# DB10012_IMUTopLevel.net
KiCad netlist of a schematic drawn in Altium Designer
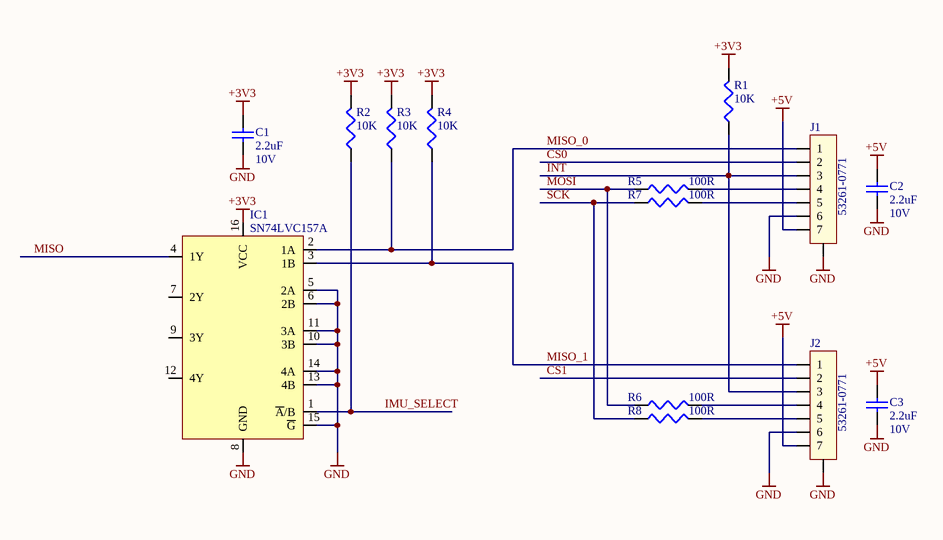
[diagram p0: DB10012_IMUTopLevel.SchDoc]

(export (version "E")
  (design (tool "Eeschema 10.0.6"))
  (components
    (comp (ref "C1")
      (value "2.2uF")
      (footprint "C0603")
      (description "Capacitor, 2.2uF, 10V, X5R")
      (fields (field (name "VOLTAGE RATING") "10V"))
      (libsource (lib "AR_Capacitors_Ceramic") (part "2.2uF/0603/CER/10V/X5R"))
    )
    (comp (ref "C2")
      (value "2.2uF")
      (footprint "C0603")
      (description "Capacitor, 2.2uF, 10V, X5R")
      (fields (field (name "VOLTAGE RATING") "10V"))
      (libsource (lib "AR_Capacitors_Ceramic") (part "2.2uF/0603/CER/10V/X5R"))
    )
    (comp (ref "C3")
      (value "2.2uF")
      (footprint "C0603")
      (description "Capacitor, 2.2uF, 10V, X5R")
      (fields (field (name "VOLTAGE RATING") "10V"))
      (libsource (lib "AR_Capacitors_Ceramic") (part "2.2uF/0603/CER/10V/X5R"))
    )
    (comp (ref "IC1")
      (value "SN74LVC157A")
      (footprint "TSSOP16")
      (description "8:4 DATA SELECTOR/MUX")
      (libsource (lib "AR_ICs") (part "SN74LVC157A"))
    )
    (comp (ref "J1")
      (value "53261-0771")
      (footprint "53261-0771")
      (description "PicoBlade 53261 Series, 7Pin, Right Angle")
      (libsource (lib "AR_Connectors") (part "53261-0771"))
    )
    (comp (ref "J2")
      (value "53261-0771")
      (footprint "53261-0771")
      (description "PicoBlade 53261 Series, 7Pin, Right Angle")
      (libsource (lib "AR_Connectors") (part "53261-0771"))
    )
    (comp (ref "R1")
      (value "10K")
      (footprint "0603")
      (description "Resistor, 10K, 1%, 0.063W, 50V, 100PPM, 0603")
      (libsource (lib "AR_Resistors_SMD") (part "10K/0603/0063W/50V"))
    )
    (comp (ref "R2")
      (value "10K")
      (footprint "0603")
      (description "Resistor, 10K, 1%, 0.063W, 50V, 100PPM, 0603")
      (libsource (lib "AR_Resistors_SMD") (part "10K/0603/0063W/50V"))
    )
    (comp (ref "R3")
      (value "10K")
      (footprint "0603")
      (description "Resistor, 10K, 1%, 0.063W, 50V, 100PPM, 0603")
      (libsource (lib "AR_Resistors_SMD") (part "10K/0603/0063W/50V"))
    )
    (comp (ref "R4")
      (value "10K")
      (footprint "0603")
      (description "Resistor, 10K, 1%, 0.063W, 50V, 100PPM, 0603")
      (libsource (lib "AR_Resistors_SMD") (part "10K/0603/0063W/50V"))
    )
    (comp (ref "R5")
      (value "100R")
      (footprint "0603")
      (description "Resistor, 100R, 1%, 0.063W, 50V, 200PPM, 0603")
      (libsource (lib "AR_Resistors_SMD") (part "100/0603/0063W/50V"))
    )
    (comp (ref "R6")
      (value "100R")
      (footprint "0603")
      (description "Resistor, 100R, 1%, 0.063W, 50V, 200PPM, 0603")
      (libsource (lib "AR_Resistors_SMD") (part "100/0603/0063W/50V"))
    )
    (comp (ref "R7")
      (value "100R")
      (footprint "0603")
      (description "Resistor, 100R, 1%, 0.063W, 50V, 200PPM, 0603")
      (libsource (lib "AR_Resistors_SMD") (part "100/0603/0063W/50V"))
    )
    (comp (ref "R8")
      (value "100R")
      (footprint "0603")
      (description "Resistor, 100R, 1%, 0.063W, 50V, 200PPM, 0603")
      (libsource (lib "AR_Resistors_SMD") (part "100/0603/0063W/50V"))
    )
  )
  (nets
    (net (code "1") (name "+3V3") (class "Default")
      (node (ref "C1") (pin "2") (pinfunction "2_2") (pintype "passive"))
      (node (ref "IC1") (pin "16") (pinfunction "VCC_16") (pintype "passive"))
      (node (ref "R1") (pin "2") (pinfunction "2_2") (pintype "passive"))
      (node (ref "R2") (pin "2") (pinfunction "2_2") (pintype "passive"))
      (node (ref "R3") (pin "2") (pinfunction "2_2") (pintype "passive"))
      (node (ref "R4") (pin "2") (pinfunction "2_2") (pintype "passive"))
    )
    (net (code "2") (name "+5V") (class "Default")
      (node (ref "C2") (pin "2") (pinfunction "2_2") (pintype "passive"))
      (node (ref "C3") (pin "2") (pinfunction "2_2") (pintype "passive"))
      (node (ref "J1") (pin "7") (pinfunction "7_7") (pintype "passive"))
      (node (ref "J2") (pin "7") (pinfunction "7_7") (pintype "passive"))
    )
    (net (code "3") (name "/CS0") (class "Default")
      (node (ref "J1") (pin "2") (pinfunction "2_2") (pintype "passive"))
    )
    (net (code "4") (name "/CS1") (class "Default")
      (node (ref "J2") (pin "2") (pinfunction "2_2") (pintype "passive"))
    )
    (net (code "5") (name "/IMU_SELECT") (class "Default")
      (node (ref "IC1") (pin "1") (pinfunction "~{A}/B_1") (pintype "passive"))
      (node (ref "R2") (pin "1") (pinfunction "1_1") (pintype "passive"))
    )
    (net (code "6") (name "/INT") (class "Default")
      (node (ref "J1") (pin "3") (pinfunction "3_3") (pintype "passive"))
      (node (ref "J2") (pin "3") (pinfunction "3_3") (pintype "passive"))
      (node (ref "R1") (pin "1") (pinfunction "1_1") (pintype "passive"))
    )
    (net (code "7") (name "/MISO") (class "Default")
      (node (ref "IC1") (pin "4") (pinfunction "1Y_4") (pintype "passive"))
    )
    (net (code "8") (name "/MISO_0") (class "Default")
      (node (ref "IC1") (pin "2") (pinfunction "1A_2") (pintype "passive"))
      (node (ref "J1") (pin "1") (pinfunction "1_1") (pintype "passive"))
      (node (ref "R3") (pin "1") (pinfunction "1_1") (pintype "passive"))
    )
    (net (code "9") (name "/MISO_1") (class "Default")
      (node (ref "IC1") (pin "3") (pinfunction "1B_3") (pintype "passive"))
      (node (ref "J2") (pin "1") (pinfunction "1_1") (pintype "passive"))
      (node (ref "R4") (pin "1") (pinfunction "1_1") (pintype "passive"))
    )
    (net (code "10") (name "/MOSI") (class "Default")
      (node (ref "R5") (pin "1") (pinfunction "1_1") (pintype "passive"))
      (node (ref "R6") (pin "1") (pinfunction "1_1") (pintype "passive"))
    )
    (net (code "11") (name "/SCK") (class "Default")
      (node (ref "R7") (pin "1") (pinfunction "1_1") (pintype "passive"))
      (node (ref "R8") (pin "1") (pinfunction "1_1") (pintype "passive"))
    )
    (net (code "12") (name "GND") (class "Default")
      (node (ref "C1") (pin "1") (pinfunction "1_1") (pintype "passive"))
      (node (ref "C2") (pin "1") (pinfunction "1_1") (pintype "passive"))
      (node (ref "C3") (pin "1") (pinfunction "1_1") (pintype "passive"))
      (node (ref "IC1") (pin "10") (pinfunction "3B_10") (pintype "passive"))
      (node (ref "IC1") (pin "11") (pinfunction "3A_11") (pintype "passive"))
      (node (ref "IC1") (pin "13") (pinfunction "4B_13") (pintype "passive"))
      (node (ref "IC1") (pin "14") (pinfunction "4A_14") (pintype "passive"))
      (node (ref "IC1") (pin "15") (pinfunction "~{G}_15") (pintype "passive"))
      (node (ref "IC1") (pin "5") (pinfunction "2A_5") (pintype "passive"))
      (node (ref "IC1") (pin "6") (pinfunction "2B_6") (pintype "passive"))
      (node (ref "IC1") (pin "8") (pinfunction "GND_8") (pintype "passive"))
      (node (ref "J1") (pin "0") (pinfunction "SHLD_0") (pintype "passive"))
      (node (ref "J1") (pin "6") (pinfunction "6_6") (pintype "passive"))
      (node (ref "J2") (pin "0") (pinfunction "SHLD_0") (pintype "passive"))
      (node (ref "J2") (pin "6") (pinfunction "6_6") (pintype "passive"))
    )
    (net (code "13") (name "Net-(J1-Pad4)") (class "Default")
      (node (ref "J1") (pin "4") (pinfunction "4_4") (pintype "passive"))
      (node (ref "R5") (pin "2") (pinfunction "2_2") (pintype "passive"))
    )
    (net (code "14") (name "Net-(J1-Pad5)") (class "Default")
      (node (ref "J1") (pin "5") (pinfunction "5_5") (pintype "passive"))
      (node (ref "R7") (pin "2") (pinfunction "2_2") (pintype "passive"))
    )
    (net (code "15") (name "Net-(J2-Pad4)") (class "Default")
      (node (ref "J2") (pin "4") (pinfunction "4_4") (pintype "passive"))
      (node (ref "R6") (pin "2") (pinfunction "2_2") (pintype "passive"))
    )
    (net (code "16") (name "Net-(J2-Pad5)") (class "Default")
      (node (ref "J2") (pin "5") (pinfunction "5_5") (pintype "passive"))
      (node (ref "R8") (pin "2") (pinfunction "2_2") (pintype "passive"))
    )
    (net (code "17") (name "unconnected-(IC1-2Y-Pad7)") (class "Default")
      (node (ref "IC1") (pin "7") (pinfunction "2Y_7") (pintype "passive"))
    )
    (net (code "18") (name "unconnected-(IC1-3Y-Pad9)") (class "Default")
      (node (ref "IC1") (pin "9") (pinfunction "3Y_9") (pintype "passive"))
    )
    (net (code "19") (name "unconnected-(IC1-4Y-Pad12)") (class "Default")
      (node (ref "IC1") (pin "12") (pinfunction "4Y_12") (pintype "passive"))
    )
  )
)
